# MiSTer_LLOAD.net
KiCad netlist of a schematic drawn in EAGLE
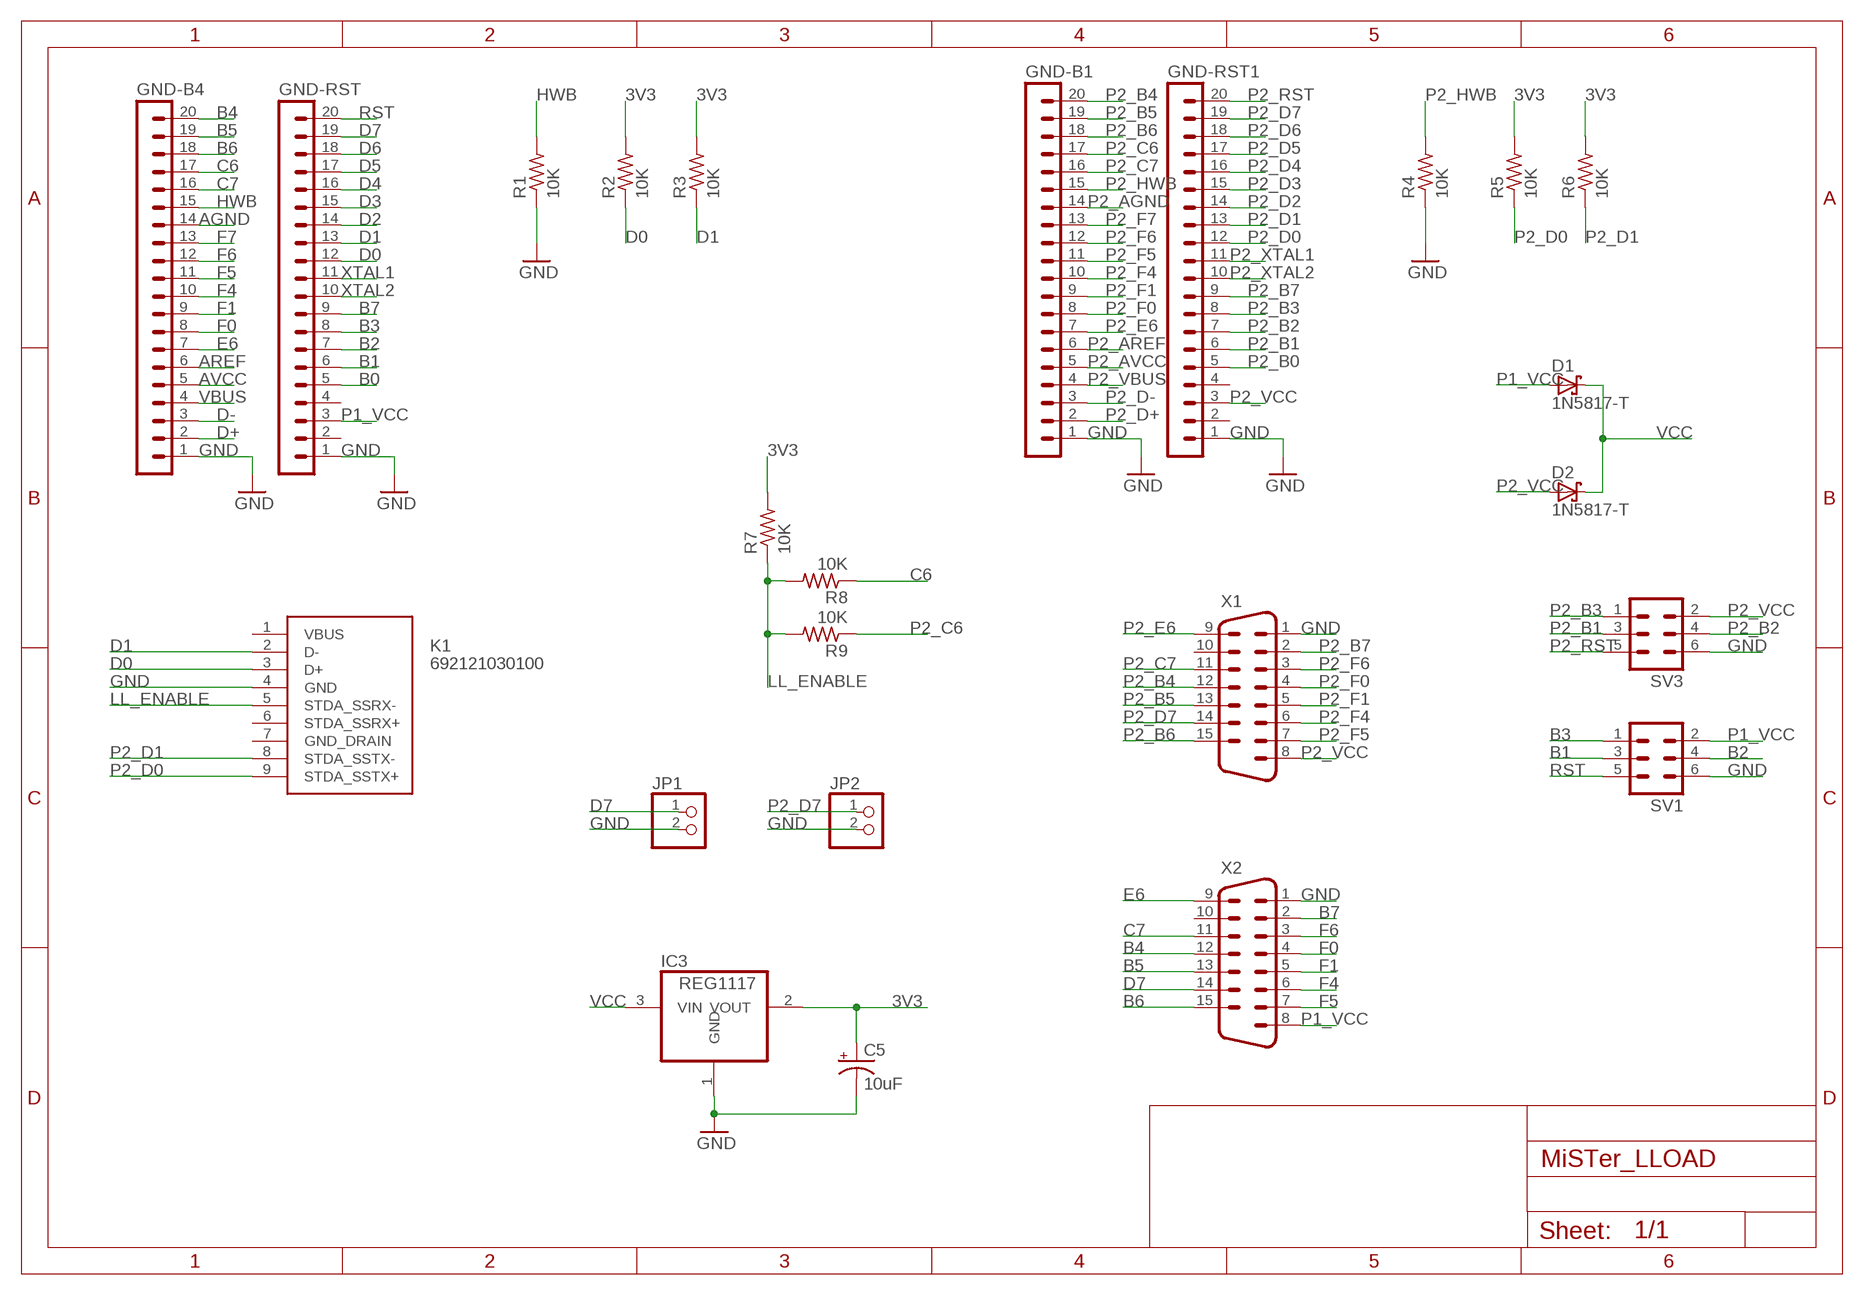
[diagram p0: schematic, sheet 1]

(export (version "E")
  (design (tool "Eeschema 10.0.6"))
  (components
    (comp (ref "C5")
      (value "10uF")
      (footprint "eagle-import:E2,5-6")
      (libsource (lib "eagle-import") (part "CPOL-USE2.5-6"))
    )
    (comp (ref "D1")
      (value "1N5817-T")
      (footprint "eagle-import:DO41-7.6")
      (libsource (lib "eagle-import") (part "1N5817-T"))
    )
    (comp (ref "D2")
      (value "1N5817-T")
      (footprint "eagle-import:DO41-7.6")
      (libsource (lib "eagle-import") (part "1N5817-T"))
    )
    (comp (ref "GND-B1")
      (value "MA20-1")
      (footprint "eagle-import:MA20-1")
      (libsource (lib "eagle-import") (part "MA20-1"))
    )
    (comp (ref "GND-B4")
      (value "MA20-1")
      (footprint "eagle-import:MA20-1")
      (libsource (lib "eagle-import") (part "MA20-1"))
    )
    (comp (ref "GND-RST")
      (value "MA20-1")
      (footprint "eagle-import:MA20-1")
      (libsource (lib "eagle-import") (part "MA20-1"))
    )
    (comp (ref "GND-RST1")
      (value "MA20-1")
      (footprint "eagle-import:MA20-1")
      (libsource (lib "eagle-import") (part "MA20-1"))
    )
    (comp (ref "IC3")
      (value "REG1117")
      (footprint "eagle-import:SOT223")
      (libsource (lib "eagle-import") (part "REG1117"))
    )
    (comp (ref "JP1")
      (value "PINHD-1X2")
      (footprint "eagle-import:1X02")
      (libsource (lib "eagle-import") (part "PINHD-1X2"))
    )
    (comp (ref "JP2")
      (value "PINHD-1X2")
      (footprint "eagle-import:1X02")
      (libsource (lib "eagle-import") (part "PINHD-1X2"))
    )
    (comp (ref "K1")
      (value "692121030100")
      (footprint "eagle-import:692121030100")
      (libsource (lib "eagle-import") (part "692121030100"))
    )
    (comp (ref "R1")
      (value "10K")
      (footprint "eagle-import:0207_10")
      (libsource (lib "eagle-import") (part "R-US_0207/10"))
    )
    (comp (ref "R2")
      (value "10K")
      (footprint "eagle-import:0207_10")
      (libsource (lib "eagle-import") (part "R-US_0207/10"))
    )
    (comp (ref "R3")
      (value "10K")
      (footprint "eagle-import:0207_10")
      (libsource (lib "eagle-import") (part "R-US_0207/10"))
    )
    (comp (ref "R4")
      (value "10K")
      (footprint "eagle-import:0207_10")
      (libsource (lib "eagle-import") (part "R-US_0207/10"))
    )
    (comp (ref "R5")
      (value "10K")
      (footprint "eagle-import:0207_10")
      (libsource (lib "eagle-import") (part "R-US_0207/10"))
    )
    (comp (ref "R6")
      (value "10K")
      (footprint "eagle-import:0207_10")
      (libsource (lib "eagle-import") (part "R-US_0207/10"))
    )
    (comp (ref "R7")
      (value "10K")
      (footprint "eagle-import:0207_10")
      (libsource (lib "eagle-import") (part "R-US_0207/10"))
    )
    (comp (ref "R8")
      (value "10K")
      (footprint "eagle-import:0207_10")
      (libsource (lib "eagle-import") (part "R-US_0207/10"))
    )
    (comp (ref "R9")
      (value "10K")
      (footprint "eagle-import:0207_10")
      (libsource (lib "eagle-import") (part "R-US_0207/10"))
    )
    (comp (ref "SV1")
      (value "MA03-2")
      (footprint "eagle-import:MA03-2")
      (libsource (lib "eagle-import") (part "MA03-2"))
    )
    (comp (ref "SV3")
      (value "MA03-2")
      (footprint "eagle-import:MA03-2")
      (libsource (lib "eagle-import") (part "MA03-2"))
    )
    (comp (ref "X1")
      (value "M15HP")
      (footprint "eagle-import:M15HP")
      (libsource (lib "eagle-import") (part "M15HP"))
    )
    (comp (ref "X2")
      (value "M15HP")
      (footprint "eagle-import:M15HP")
      (libsource (lib "eagle-import") (part "M15HP"))
    )
  )
  (nets
    (net (code "1") (name "/3V3") (class "Default")
      (node (ref "C5") (pin "+") (pinfunction "+_+") (pintype "passive"))
      (node (ref "IC3") (pin "2") (pinfunction "VOUT_2") (pintype "output"))
      (node (ref "R2") (pin "2") (pinfunction "2_2") (pintype "passive"))
      (node (ref "R3") (pin "2") (pinfunction "2_2") (pintype "passive"))
      (node (ref "R5") (pin "2") (pinfunction "2_2") (pintype "passive"))
      (node (ref "R6") (pin "2") (pinfunction "2_2") (pintype "passive"))
      (node (ref "R7") (pin "2") (pinfunction "2_2") (pintype "passive"))
    )
    (net (code "2") (name "/AGND") (class "Default")
      (node (ref "GND-B4") (pin "14") (pinfunction "14_14") (pintype "passive"))
    )
    (net (code "3") (name "/AREF") (class "Default")
      (node (ref "GND-B4") (pin "6") (pinfunction "6_6") (pintype "passive"))
    )
    (net (code "4") (name "/AVCC") (class "Default")
      (node (ref "GND-B4") (pin "5") (pinfunction "5_5") (pintype "passive"))
    )
    (net (code "5") (name "/B0") (class "Default")
      (node (ref "GND-RST") (pin "5") (pinfunction "5_5") (pintype "passive"))
    )
    (net (code "6") (name "/B1") (class "Default")
      (node (ref "GND-RST") (pin "6") (pinfunction "6_6") (pintype "passive"))
      (node (ref "SV1") (pin "3") (pinfunction "3_3") (pintype "passive"))
    )
    (net (code "7") (name "/B2") (class "Default")
      (node (ref "GND-RST") (pin "7") (pinfunction "7_7") (pintype "passive"))
      (node (ref "SV1") (pin "4") (pinfunction "4_4") (pintype "passive"))
    )
    (net (code "8") (name "/B3") (class "Default")
      (node (ref "GND-RST") (pin "8") (pinfunction "8_8") (pintype "passive"))
      (node (ref "SV1") (pin "1") (pinfunction "1_1") (pintype "passive"))
    )
    (net (code "9") (name "/B4") (class "Default")
      (node (ref "GND-B4") (pin "20") (pinfunction "20_20") (pintype "passive"))
      (node (ref "X2") (pin "12") (pinfunction "12_12") (pintype "passive"))
    )
    (net (code "10") (name "/B5") (class "Default")
      (node (ref "GND-B4") (pin "19") (pinfunction "19_19") (pintype "passive"))
      (node (ref "X2") (pin "13") (pinfunction "13_13") (pintype "passive"))
    )
    (net (code "11") (name "/B6") (class "Default")
      (node (ref "GND-B4") (pin "18") (pinfunction "18_18") (pintype "passive"))
      (node (ref "X2") (pin "15") (pinfunction "15_15") (pintype "passive"))
    )
    (net (code "12") (name "/B7") (class "Default")
      (node (ref "GND-RST") (pin "9") (pinfunction "9_9") (pintype "passive"))
      (node (ref "X2") (pin "2") (pinfunction "2_2") (pintype "passive"))
    )
    (net (code "13") (name "/C6") (class "Default")
      (node (ref "GND-B4") (pin "17") (pinfunction "17_17") (pintype "passive"))
      (node (ref "R8") (pin "1") (pinfunction "1_1") (pintype "passive"))
    )
    (net (code "14") (name "/C7") (class "Default")
      (node (ref "GND-B4") (pin "16") (pinfunction "16_16") (pintype "passive"))
      (node (ref "X2") (pin "11") (pinfunction "11_11") (pintype "passive"))
    )
    (net (code "15") (name "/D+") (class "Default")
      (node (ref "GND-B4") (pin "2") (pinfunction "2_2") (pintype "passive"))
    )
    (net (code "16") (name "/D-") (class "Default")
      (node (ref "GND-B4") (pin "3") (pinfunction "3_3") (pintype "passive"))
    )
    (net (code "17") (name "/D0") (class "Default")
      (node (ref "GND-RST") (pin "12") (pinfunction "12_12") (pintype "passive"))
      (node (ref "K1") (pin "3") (pinfunction "D+_3") (pintype "bidirectional"))
      (node (ref "R2") (pin "1") (pinfunction "1_1") (pintype "passive"))
    )
    (net (code "18") (name "/D1") (class "Default")
      (node (ref "GND-RST") (pin "13") (pinfunction "13_13") (pintype "passive"))
      (node (ref "K1") (pin "2") (pinfunction "D-_2") (pintype "bidirectional"))
      (node (ref "R3") (pin "1") (pinfunction "1_1") (pintype "passive"))
    )
    (net (code "19") (name "/D2") (class "Default")
      (node (ref "GND-RST") (pin "14") (pinfunction "14_14") (pintype "passive"))
    )
    (net (code "20") (name "/D3") (class "Default")
      (node (ref "GND-RST") (pin "15") (pinfunction "15_15") (pintype "passive"))
    )
    (net (code "21") (name "/D4") (class "Default")
      (node (ref "GND-RST") (pin "16") (pinfunction "16_16") (pintype "passive"))
    )
    (net (code "22") (name "/D5") (class "Default")
      (node (ref "GND-RST") (pin "17") (pinfunction "17_17") (pintype "passive"))
    )
    (net (code "23") (name "/D6") (class "Default")
      (node (ref "GND-RST") (pin "18") (pinfunction "18_18") (pintype "passive"))
    )
    (net (code "24") (name "/D7") (class "Default")
      (node (ref "GND-RST") (pin "19") (pinfunction "19_19") (pintype "passive"))
      (node (ref "JP1") (pin "1") (pinfunction "1_1") (pintype "passive"))
      (node (ref "X2") (pin "14") (pinfunction "14_14") (pintype "passive"))
    )
    (net (code "25") (name "/E6") (class "Default")
      (node (ref "GND-B4") (pin "7") (pinfunction "7_7") (pintype "passive"))
      (node (ref "X2") (pin "9") (pinfunction "9_9") (pintype "passive"))
    )
    (net (code "26") (name "/F0") (class "Default")
      (node (ref "GND-B4") (pin "8") (pinfunction "8_8") (pintype "passive"))
      (node (ref "X2") (pin "4") (pinfunction "4_4") (pintype "passive"))
    )
    (net (code "27") (name "/F1") (class "Default")
      (node (ref "GND-B4") (pin "9") (pinfunction "9_9") (pintype "passive"))
      (node (ref "X2") (pin "5") (pinfunction "5_5") (pintype "passive"))
    )
    (net (code "28") (name "/F4") (class "Default")
      (node (ref "GND-B4") (pin "10") (pinfunction "10_10") (pintype "passive"))
      (node (ref "X2") (pin "6") (pinfunction "6_6") (pintype "passive"))
    )
    (net (code "29") (name "/F5") (class "Default")
      (node (ref "GND-B4") (pin "11") (pinfunction "11_11") (pintype "passive"))
      (node (ref "X2") (pin "7") (pinfunction "7_7") (pintype "passive"))
    )
    (net (code "30") (name "/F6") (class "Default")
      (node (ref "GND-B4") (pin "12") (pinfunction "12_12") (pintype "passive"))
      (node (ref "X2") (pin "3") (pinfunction "3_3") (pintype "passive"))
    )
    (net (code "31") (name "/F7") (class "Default")
      (node (ref "GND-B4") (pin "13") (pinfunction "13_13") (pintype "passive"))
    )
    (net (code "32") (name "/HWB") (class "Default")
      (node (ref "GND-B4") (pin "15") (pinfunction "15_15") (pintype "passive"))
      (node (ref "R1") (pin "2") (pinfunction "2_2") (pintype "passive"))
    )
    (net (code "33") (name "/LL_ENABLE") (class "Default")
      (node (ref "K1") (pin "5") (pinfunction "STDA_SSRX-_5") (pintype "bidirectional"))
      (node (ref "R7") (pin "1") (pinfunction "1_1") (pintype "passive"))
      (node (ref "R8") (pin "2") (pinfunction "2_2") (pintype "passive"))
      (node (ref "R9") (pin "2") (pinfunction "2_2") (pintype "passive"))
    )
    (net (code "34") (name "/P1_VCC") (class "Default")
      (node (ref "D1") (pin "A") (pinfunction "A_A") (pintype "passive"))
      (node (ref "GND-RST") (pin "3") (pinfunction "3_3") (pintype "passive"))
      (node (ref "SV1") (pin "2") (pinfunction "2_2") (pintype "passive"))
      (node (ref "X2") (pin "8") (pinfunction "8_8") (pintype "passive"))
    )
    (net (code "35") (name "/P2_AGND") (class "Default")
      (node (ref "GND-B1") (pin "14") (pinfunction "14_14") (pintype "passive"))
    )
    (net (code "36") (name "/P2_AREF") (class "Default")
      (node (ref "GND-B1") (pin "6") (pinfunction "6_6") (pintype "passive"))
    )
    (net (code "37") (name "/P2_AVCC") (class "Default")
      (node (ref "GND-B1") (pin "5") (pinfunction "5_5") (pintype "passive"))
    )
    (net (code "38") (name "/P2_B0") (class "Default")
      (node (ref "GND-RST1") (pin "5") (pinfunction "5_5") (pintype "passive"))
    )
    (net (code "39") (name "/P2_B1") (class "Default")
      (node (ref "GND-RST1") (pin "6") (pinfunction "6_6") (pintype "passive"))
      (node (ref "SV3") (pin "3") (pinfunction "3_3") (pintype "passive"))
    )
    (net (code "40") (name "/P2_B2") (class "Default")
      (node (ref "GND-RST1") (pin "7") (pinfunction "7_7") (pintype "passive"))
      (node (ref "SV3") (pin "4") (pinfunction "4_4") (pintype "passive"))
    )
    (net (code "41") (name "/P2_B3") (class "Default")
      (node (ref "GND-RST1") (pin "8") (pinfunction "8_8") (pintype "passive"))
      (node (ref "SV3") (pin "1") (pinfunction "1_1") (pintype "passive"))
    )
    (net (code "42") (name "/P2_B4") (class "Default")
      (node (ref "GND-B1") (pin "20") (pinfunction "20_20") (pintype "passive"))
      (node (ref "X1") (pin "12") (pinfunction "12_12") (pintype "passive"))
    )
    (net (code "43") (name "/P2_B5") (class "Default")
      (node (ref "GND-B1") (pin "19") (pinfunction "19_19") (pintype "passive"))
      (node (ref "X1") (pin "13") (pinfunction "13_13") (pintype "passive"))
    )
    (net (code "44") (name "/P2_B6") (class "Default")
      (node (ref "GND-B1") (pin "18") (pinfunction "18_18") (pintype "passive"))
      (node (ref "X1") (pin "15") (pinfunction "15_15") (pintype "passive"))
    )
    (net (code "45") (name "/P2_B7") (class "Default")
      (node (ref "GND-RST1") (pin "9") (pinfunction "9_9") (pintype "passive"))
      (node (ref "X1") (pin "2") (pinfunction "2_2") (pintype "passive"))
    )
    (net (code "46") (name "/P2_C6") (class "Default")
      (node (ref "GND-B1") (pin "17") (pinfunction "17_17") (pintype "passive"))
      (node (ref "R9") (pin "1") (pinfunction "1_1") (pintype "passive"))
    )
    (net (code "47") (name "/P2_C7") (class "Default")
      (node (ref "GND-B1") (pin "16") (pinfunction "16_16") (pintype "passive"))
      (node (ref "X1") (pin "11") (pinfunction "11_11") (pintype "passive"))
    )
    (net (code "48") (name "/P2_D+") (class "Default")
      (node (ref "GND-B1") (pin "2") (pinfunction "2_2") (pintype "passive"))
    )
    (net (code "49") (name "/P2_D-") (class "Default")
      (node (ref "GND-B1") (pin "3") (pinfunction "3_3") (pintype "passive"))
    )
    (net (code "50") (name "/P2_D0") (class "Default")
      (node (ref "GND-RST1") (pin "12") (pinfunction "12_12") (pintype "passive"))
      (node (ref "K1") (pin "9") (pinfunction "STDA_SSTX+_9") (pintype "bidirectional"))
      (node (ref "R5") (pin "1") (pinfunction "1_1") (pintype "passive"))
    )
    (net (code "51") (name "/P2_D1") (class "Default")
      (node (ref "GND-RST1") (pin "13") (pinfunction "13_13") (pintype "passive"))
      (node (ref "K1") (pin "8") (pinfunction "STDA_SSTX-_8") (pintype "bidirectional"))
      (node (ref "R6") (pin "1") (pinfunction "1_1") (pintype "passive"))
    )
    (net (code "52") (name "/P2_D2") (class "Default")
      (node (ref "GND-RST1") (pin "14") (pinfunction "14_14") (pintype "passive"))
    )
    (net (code "53") (name "/P2_D3") (class "Default")
      (node (ref "GND-RST1") (pin "15") (pinfunction "15_15") (pintype "passive"))
    )
    (net (code "54") (name "/P2_D4") (class "Default")
      (node (ref "GND-RST1") (pin "16") (pinfunction "16_16") (pintype "passive"))
    )
    (net (code "55") (name "/P2_D5") (class "Default")
      (node (ref "GND-RST1") (pin "17") (pinfunction "17_17") (pintype "passive"))
    )
    (net (code "56") (name "/P2_D6") (class "Default")
      (node (ref "GND-RST1") (pin "18") (pinfunction "18_18") (pintype "passive"))
    )
    (net (code "57") (name "/P2_D7") (class "Default")
      (node (ref "GND-RST1") (pin "19") (pinfunction "19_19") (pintype "passive"))
      (node (ref "JP2") (pin "1") (pinfunction "1_1") (pintype "passive"))
      (node (ref "X1") (pin "14") (pinfunction "14_14") (pintype "passive"))
    )
    (net (code "58") (name "/P2_E6") (class "Default")
      (node (ref "GND-B1") (pin "7") (pinfunction "7_7") (pintype "passive"))
      (node (ref "X1") (pin "9") (pinfunction "9_9") (pintype "passive"))
    )
    (net (code "59") (name "/P2_F0") (class "Default")
      (node (ref "GND-B1") (pin "8") (pinfunction "8_8") (pintype "passive"))
      (node (ref "X1") (pin "4") (pinfunction "4_4") (pintype "passive"))
    )
    (net (code "60") (name "/P2_F1") (class "Default")
      (node (ref "GND-B1") (pin "9") (pinfunction "9_9") (pintype "passive"))
      (node (ref "X1") (pin "5") (pinfunction "5_5") (pintype "passive"))
    )
    (net (code "61") (name "/P2_F4") (class "Default")
      (node (ref "GND-B1") (pin "10") (pinfunction "10_10") (pintype "passive"))
      (node (ref "X1") (pin "6") (pinfunction "6_6") (pintype "passive"))
    )
    (net (code "62") (name "/P2_F5") (class "Default")
      (node (ref "GND-B1") (pin "11") (pinfunction "11_11") (pintype "passive"))
      (node (ref "X1") (pin "7") (pinfunction "7_7") (pintype "passive"))
    )
    (net (code "63") (name "/P2_F6") (class "Default")
      (node (ref "GND-B1") (pin "12") (pinfunction "12_12") (pintype "passive"))
      (node (ref "X1") (pin "3") (pinfunction "3_3") (pintype "passive"))
    )
    (net (code "64") (name "/P2_F7") (class "Default")
      (node (ref "GND-B1") (pin "13") (pinfunction "13_13") (pintype "passive"))
    )
    (net (code "65") (name "/P2_HWB") (class "Default")
      (node (ref "GND-B1") (pin "15") (pinfunction "15_15") (pintype "passive"))
      (node (ref "R4") (pin "2") (pinfunction "2_2") (pintype "passive"))
    )
    (net (code "66") (name "/P2_RST") (class "Default")
      (node (ref "GND-RST1") (pin "20") (pinfunction "20_20") (pintype "passive"))
      (node (ref "SV3") (pin "5") (pinfunction "5_5") (pintype "passive"))
    )
    (net (code "67") (name "/P2_VBUS") (class "Default")
      (node (ref "GND-B1") (pin "4") (pinfunction "4_4") (pintype "passive"))
    )
    (net (code "68") (name "/P2_VCC") (class "Default")
      (node (ref "D2") (pin "A") (pinfunction "A_A") (pintype "passive"))
      (node (ref "GND-RST1") (pin "3") (pinfunction "3_3") (pintype "passive"))
      (node (ref "SV3") (pin "2") (pinfunction "2_2") (pintype "passive"))
      (node (ref "X1") (pin "8") (pinfunction "8_8") (pintype "passive"))
    )
    (net (code "69") (name "/P2_XTAL1") (class "Default")
      (node (ref "GND-RST1") (pin "11") (pinfunction "11_11") (pintype "passive"))
    )
    (net (code "70") (name "/P2_XTAL2") (class "Default")
      (node (ref "GND-RST1") (pin "10") (pinfunction "10_10") (pintype "passive"))
    )
    (net (code "71") (name "/RST") (class "Default")
      (node (ref "GND-RST") (pin "20") (pinfunction "20_20") (pintype "passive"))
      (node (ref "SV1") (pin "5") (pinfunction "5_5") (pintype "passive"))
    )
    (net (code "72") (name "/VBUS") (class "Default")
      (node (ref "GND-B4") (pin "4") (pinfunction "4_4") (pintype "passive"))
    )
    (net (code "73") (name "/VCC") (class "Default")
      (node (ref "D1") (pin "C") (pinfunction "C_C") (pintype "passive"))
      (node (ref "D2") (pin "C") (pinfunction "C_C") (pintype "passive"))
      (node (ref "IC3") (pin "3") (pinfunction "VIN_3") (pintype "input"))
    )
    (net (code "74") (name "/XTAL1") (class "Default")
      (node (ref "GND-RST") (pin "11") (pinfunction "11_11") (pintype "passive"))
    )
    (net (code "75") (name "/XTAL2") (class "Default")
      (node (ref "GND-RST") (pin "10") (pinfunction "10_10") (pintype "passive"))
    )
    (net (code "76") (name "GND") (class "Default")
      (node (ref "C5") (pin "-") (pinfunction "-_-") (pintype "passive"))
      (node (ref "GND-B1") (pin "1") (pinfunction "1_1") (pintype "passive"))
      (node (ref "GND-B4") (pin "1") (pinfunction "1_1") (pintype "passive"))
      (node (ref "GND-RST") (pin "1") (pinfunction "1_1") (pintype "passive"))
      (node (ref "GND-RST1") (pin "1") (pinfunction "1_1") (pintype "passive"))
      (node (ref "IC3") (pin "1") (pinfunction "GND_1") (pintype "power_in"))
      (node (ref "JP1") (pin "2") (pinfunction "2_2") (pintype "passive"))
      (node (ref "JP2") (pin "2") (pinfunction "2_2") (pintype "passive"))
      (node (ref "K1") (pin "4") (pinfunction "GND_4") (pintype "bidirectional"))
      (node (ref "R1") (pin "1") (pinfunction "1_1") (pintype "passive"))
      (node (ref "R4") (pin "1") (pinfunction "1_1") (pintype "passive"))
      (node (ref "SV1") (pin "6") (pinfunction "6_6") (pintype "passive"))
      (node (ref "SV3") (pin "6") (pinfunction "6_6") (pintype "passive"))
      (node (ref "X1") (pin "1") (pinfunction "1_1") (pintype "passive"))
      (node (ref "X2") (pin "1") (pinfunction "1_1") (pintype "passive"))
    )
    (net (code "77") (name "unconnected-(GND-RST-Pad2)") (class "Default")
      (node (ref "GND-RST") (pin "2") (pinfunction "2_2") (pintype "passive"))
    )
    (net (code "78") (name "unconnected-(GND-RST-Pad4)") (class "Default")
      (node (ref "GND-RST") (pin "4") (pinfunction "4_4") (pintype "passive"))
    )
    (net (code "79") (name "unconnected-(GND-RST1-Pad2)") (class "Default")
      (node (ref "GND-RST1") (pin "2") (pinfunction "2_2") (pintype "passive"))
    )
    (net (code "80") (name "unconnected-(GND-RST1-Pad4)") (class "Default")
      (node (ref "GND-RST1") (pin "4") (pinfunction "4_4") (pintype "passive"))
    )
    (net (code "81") (name "unconnected-(K1-GND_DRAIN-Pad7)") (class "Default")
      (node (ref "K1") (pin "7") (pinfunction "GND_DRAIN_7") (pintype "bidirectional"))
    )
    (net (code "82") (name "unconnected-(K1-STDA_SSRX+-Pad6)") (class "Default")
      (node (ref "K1") (pin "6") (pinfunction "STDA_SSRX+_6") (pintype "bidirectional"))
    )
    (net (code "83") (name "unconnected-(K1-VBUS-Pad1)") (class "Default")
      (node (ref "K1") (pin "1") (pinfunction "VBUS_1") (pintype "bidirectional"))
    )
    (net (code "84") (name "unconnected-(X1-Pad10)") (class "Default")
      (node (ref "X1") (pin "10") (pinfunction "10_10") (pintype "passive"))
    )
    (net (code "85") (name "unconnected-(X2-Pad10)") (class "Default")
      (node (ref "X2") (pin "10") (pinfunction "10_10") (pintype "passive"))
    )
  )
)
